# ATtiny841_StepperTesting.net
KiCad netlist of a schematic drawn in EAGLE
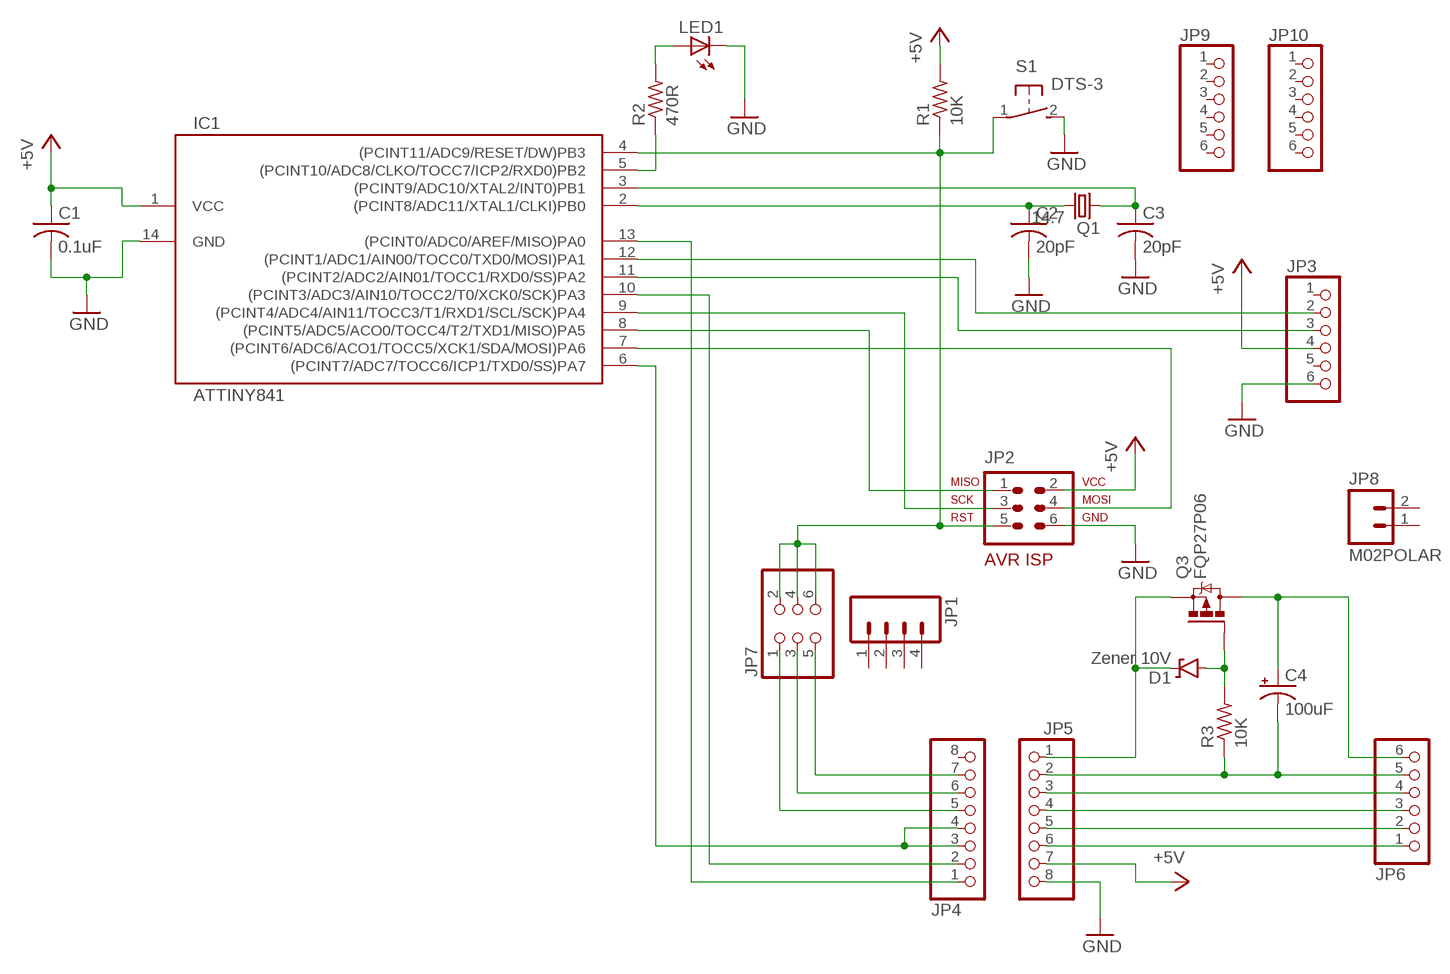
[diagram p0: schematic, sheet 1]

(export (version "E")
  (design (tool "Eeschema 10.0.6"))
  (components
    (comp (ref "C1")
      (value "0.1uF")
      (footprint "eagle-import:C025-024X044")
      (libsource (lib "eagle-import") (part "C025"))
    )
    (comp (ref "C2")
      (value "20pF")
      (footprint "eagle-import:C025-024X044")
      (libsource (lib "eagle-import") (part "C025"))
    )
    (comp (ref "C3")
      (value "20pF")
      (footprint "eagle-import:C025-024X044")
      (libsource (lib "eagle-import") (part "C025"))
    )
    (comp (ref "C4")
      (value "100uF")
      (footprint "eagle-import:E3,5-8")
      (libsource (lib "eagle-import") (part "CPOL-USE3.5-8"))
    )
    (comp (ref "D1")
      (value "Zener 10V")
      (footprint "eagle-import:DIODE-ZENER")
      (libsource (lib "eagle-import") (part "DIODE-ZENERPTH"))
    )
    (comp (ref "IC1")
      (value "ATTINY841")
      (footprint "eagle-import:SOIC14")
      (libsource (lib "eagle-import") (part "ATTINY441/841-SSU"))
    )
    (comp (ref "JP1")
      (value "M04POLAR")
      (footprint "eagle-import:MOLEX-1X4")
      (libsource (lib "eagle-import") (part "M04POLAR"))
    )
    (comp (ref "JP2")
      (value "AVR-ISP-6VERT")
      (footprint "eagle-import:AVR-ISP-6")
      (libsource (lib "eagle-import") (part "AVR-ISP-6VERT"))
    )
    (comp (ref "JP3")
      (value "PINHD-1X6CB")
      (footprint "eagle-import:1X06-CLEANBIG")
      (libsource (lib "eagle-import") (part "PINHD-1X6CB"))
    )
    (comp (ref "JP4")
      (value "PINHD-1X8CLEANBIG")
      (footprint "eagle-import:1X08-CLEANBIG")
      (libsource (lib "eagle-import") (part "PINHD-1X8CLEANBIG"))
    )
    (comp (ref "JP5")
      (value "PINHD-1X8CLEANBIG")
      (footprint "eagle-import:1X08-CLEANBIG")
      (libsource (lib "eagle-import") (part "PINHD-1X8CLEANBIG"))
    )
    (comp (ref "JP6")
      (value "PINHD-1X6CB")
      (footprint "eagle-import:1X06-CLEANBIG")
      (libsource (lib "eagle-import") (part "PINHD-1X6CB"))
    )
    (comp (ref "JP7")
      (value "PINHD-2X3")
      (footprint "eagle-import:2X03")
      (libsource (lib "eagle-import") (part "PINHD-2X3"))
    )
    (comp (ref "JP8")
      (value "M02POLAR")
      (footprint "eagle-import:MOLEX-1X2")
      (libsource (lib "eagle-import") (part "M02POLAR"))
    )
    (comp (ref "JP9")
      (value "PINHD-1X6CB")
      (footprint "eagle-import:1X06-CLEANBIG")
      (libsource (lib "eagle-import") (part "PINHD-1X6CB"))
    )
    (comp (ref "JP10")
      (value "PINHD-1X6CB")
      (footprint "eagle-import:1X06-CLEANBIG")
      (libsource (lib "eagle-import") (part "PINHD-1X6CB"))
    )
    (comp (ref "LED1")
      (value "LED5MM")
      (footprint "eagle-import:LED5MM")
      (libsource (lib "eagle-import") (part "LED5MM"))
    )
    (comp (ref "Q1")
      (value "14.7")
      (footprint "eagle-import:HC49_S")
      (libsource (lib "eagle-import") (part "CRYSTALHC49S"))
    )
    (comp (ref "Q3")
      (value "FQP27P06")
      (footprint "eagle-import:TO220BV")
      (libsource (lib "eagle-import") (part "IRF9530"))
    )
    (comp (ref "R1")
      (value "10K")
      (footprint "eagle-import:0207_7")
      (libsource (lib "eagle-import") (part "R-US_0207/7"))
    )
    (comp (ref "R2")
      (value "470R")
      (footprint "eagle-import:0207_7")
      (libsource (lib "eagle-import") (part "R-US_0207/7"))
    )
    (comp (ref "R3")
      (value "10K")
      (footprint "eagle-import:0207_7")
      (libsource (lib "eagle-import") (part "R-US_0207/7"))
    )
    (comp (ref "S1")
      (value "DTS-3")
      (footprint "eagle-import:DTS-3")
      (libsource (lib "eagle-import") (part "DTS-3"))
    )
  )
  (nets
    (net (code "1") (name "+5V") (class "Default")
      (node (ref "C1") (pin "1") (pinfunction "1_1") (pintype "passive"))
      (node (ref "IC1") (pin "1") (pinfunction "VCC_1") (pintype "bidirectional"))
      (node (ref "JP2") (pin "2") (pinfunction "2_2") (pintype "passive"))
      (node (ref "JP3") (pin "4") (pinfunction "4_4") (pintype "passive"))
      (node (ref "JP5") (pin "7") (pinfunction "7_7") (pintype "passive"))
      (node (ref "R1") (pin "2") (pinfunction "2_2") (pintype "passive"))
    )
    (net (code "2") (name "GND") (class "Default")
      (node (ref "C1") (pin "2") (pinfunction "2_2") (pintype "passive"))
      (node (ref "C2") (pin "2") (pinfunction "2_2") (pintype "passive"))
      (node (ref "C3") (pin "2") (pinfunction "2_2") (pintype "passive"))
      (node (ref "IC1") (pin "14") (pinfunction "GND_14") (pintype "bidirectional"))
      (node (ref "JP2") (pin "6") (pinfunction "6_6") (pintype "passive"))
      (node (ref "JP3") (pin "6") (pinfunction "6_6") (pintype "passive"))
      (node (ref "JP5") (pin "8") (pinfunction "8_8") (pintype "passive"))
      (node (ref "LED1") (pin "K") (pinfunction "C_K") (pintype "passive"))
      (node (ref "S1") (pin "2") (pinfunction "2_2") (pintype "passive"))
    )
    (net (code "3") (name "Net-(C4-Pad+)") (class "Default")
      (node (ref "C4") (pin "+") (pinfunction "+_+") (pintype "passive"))
      (node (ref "JP6") (pin "6") (pinfunction "6_6") (pintype "passive"))
      (node (ref "Q3") (pin "D") (pinfunction "D_D") (pintype "passive"))
    )
    (net (code "4") (name "Net-(C4-Pad-)") (class "Default")
      (node (ref "C4") (pin "-") (pinfunction "-_-") (pintype "passive"))
      (node (ref "JP5") (pin "2") (pinfunction "2_2") (pintype "passive"))
      (node (ref "JP6") (pin "5") (pinfunction "5_5") (pintype "passive"))
      (node (ref "R3") (pin "1") (pinfunction "1_1") (pintype "passive"))
    )
    (net (code "5") (name "Net-(D1-A)") (class "Default")
      (node (ref "D1") (pin "P$2") (pinfunction "A_P$2") (pintype "passive"))
      (node (ref "Q3") (pin "G") (pinfunction "G_G") (pintype "passive"))
      (node (ref "R3") (pin "2") (pinfunction "2_2") (pintype "passive"))
    )
    (net (code "6") (name "Net-(D1-C)") (class "Default")
      (node (ref "D1") (pin "P$1") (pinfunction "C_P$1") (pintype "passive"))
      (node (ref "JP5") (pin "1") (pinfunction "1_1") (pintype "passive"))
      (node (ref "Q3") (pin "S") (pinfunction "S_S") (pintype "passive"))
    )
    (net (code "7") (name "Net-(IC1-(PCINT0{slash}ADC0{slash}AREF{slash}MISO)PA0)") (class "Default")
      (node (ref "IC1") (pin "13") (pinfunction "(PCINT0/ADC0/AREF/MISO)PA0_13") (pintype "bidirectional"))
      (node (ref "JP4") (pin "1") (pinfunction "1_1") (pintype "passive"))
    )
    (net (code "8") (name "Net-(IC1-(PCINT1{slash}ADC1{slash}AIN00{slash}TOCC0{slash}TXD0{slash}MOSI)PA1)") (class "Default")
      (node (ref "IC1") (pin "12") (pinfunction "(PCINT1/ADC1/AIN00/TOCC0/TXD0/MOSI)PA1_12") (pintype "bidirectional"))
      (node (ref "JP3") (pin "2") (pinfunction "2_2") (pintype "passive"))
    )
    (net (code "9") (name "Net-(IC1-(PCINT2{slash}ADC2{slash}AIN01{slash}TOCC1{slash}RXD0{slash}SS)PA2)") (class "Default")
      (node (ref "IC1") (pin "11") (pinfunction "(PCINT2/ADC2/AIN01/TOCC1/RXD0/SS)PA2_11") (pintype "bidirectional"))
      (node (ref "JP3") (pin "3") (pinfunction "3_3") (pintype "passive"))
    )
    (net (code "10") (name "Net-(IC1-(PCINT3{slash}ADC3{slash}AIN10{slash}TOCC2{slash}T0{slash}XCK0{slash}SCK)PA3)") (class "Default")
      (node (ref "IC1") (pin "10") (pinfunction "(PCINT3/ADC3/AIN10/TOCC2/T0/XCK0/SCK)PA3_10") (pintype "bidirectional"))
      (node (ref "JP4") (pin "2") (pinfunction "2_2") (pintype "passive"))
    )
    (net (code "11") (name "Net-(IC1-(PCINT4{slash}ADC4{slash}AIN11{slash}TOCC3{slash}T1{slash}RXD1{slash}SCL{slash}SCK)PA4)") (class "Default")
      (node (ref "IC1") (pin "9") (pinfunction "(PCINT4/ADC4/AIN11/TOCC3/T1/RXD1/SCL/SCK)PA4_9") (pintype "bidirectional"))
      (node (ref "JP2") (pin "3") (pinfunction "3_3") (pintype "passive"))
    )
    (net (code "12") (name "Net-(IC1-(PCINT5{slash}ADC5{slash}ACO0{slash}TOCC4{slash}T2{slash}TXD1{slash}MISO)PA5)") (class "Default")
      (node (ref "IC1") (pin "8") (pinfunction "(PCINT5/ADC5/ACO0/TOCC4/T2/TXD1/MISO)PA5_8") (pintype "bidirectional"))
      (node (ref "JP2") (pin "1") (pinfunction "1_1") (pintype "passive"))
    )
    (net (code "13") (name "Net-(IC1-(PCINT6{slash}ADC6{slash}ACO1{slash}TOCC5{slash}XCK1{slash}SDA{slash}MOSI)PA6)") (class "Default")
      (node (ref "IC1") (pin "7") (pinfunction "(PCINT6/ADC6/ACO1/TOCC5/XCK1/SDA/MOSI)PA6_7") (pintype "bidirectional"))
      (node (ref "JP2") (pin "4") (pinfunction "4_4") (pintype "passive"))
    )
    (net (code "14") (name "Net-(IC1-(PCINT7{slash}ADC7{slash}TOCC6{slash}ICP1{slash}TXD0{slash}SS)PA7)") (class "Default")
      (node (ref "IC1") (pin "6") (pinfunction "(PCINT7/ADC7/TOCC6/ICP1/TXD0/SS)PA7_6") (pintype "bidirectional"))
      (node (ref "JP4") (pin "3") (pinfunction "3_3") (pintype "passive"))
      (node (ref "JP4") (pin "4") (pinfunction "4_4") (pintype "passive"))
    )
    (net (code "15") (name "Net-(IC1-(PCINT8{slash}ADC11{slash}XTAL1{slash}CLKI)PB0)") (class "Default")
      (node (ref "C2") (pin "1") (pinfunction "1_1") (pintype "passive"))
      (node (ref "IC1") (pin "2") (pinfunction "(PCINT8/ADC11/XTAL1/CLKI)PB0_2") (pintype "bidirectional"))
      (node (ref "Q1") (pin "2") (pinfunction "2_2") (pintype "passive"))
    )
    (net (code "16") (name "Net-(IC1-(PCINT9{slash}ADC10{slash}XTAL2{slash}INT0)PB1)") (class "Default")
      (node (ref "C3") (pin "1") (pinfunction "1_1") (pintype "passive"))
      (node (ref "IC1") (pin "3") (pinfunction "(PCINT9/ADC10/XTAL2/INT0)PB1_3") (pintype "bidirectional"))
      (node (ref "Q1") (pin "1") (pinfunction "1_1") (pintype "passive"))
    )
    (net (code "17") (name "Net-(IC1-(PCINT10{slash}ADC8{slash}CLKO{slash}TOCC7{slash}ICP2{slash}RXD0)PB2)") (class "Default")
      (node (ref "IC1") (pin "5") (pinfunction "(PCINT10/ADC8/CLKO/TOCC7/ICP2/RXD0)PB2_5") (pintype "bidirectional"))
      (node (ref "R2") (pin "1") (pinfunction "1_1") (pintype "passive"))
    )
    (net (code "18") (name "Net-(IC1-(PCINT11{slash}ADC9{slash}RESET{slash}DW)PB3)") (class "Default")
      (node (ref "IC1") (pin "4") (pinfunction "(PCINT11/ADC9/RESET/DW)PB3_4") (pintype "bidirectional"))
      (node (ref "JP2") (pin "5") (pinfunction "5_5") (pintype "passive"))
      (node (ref "JP7") (pin "2") (pinfunction "2_2") (pintype "passive"))
      (node (ref "JP7") (pin "4") (pinfunction "4_4") (pintype "passive"))
      (node (ref "JP7") (pin "6") (pinfunction "6_6") (pintype "passive"))
      (node (ref "R1") (pin "1") (pinfunction "1_1") (pintype "passive"))
      (node (ref "S1") (pin "1") (pinfunction "1_1") (pintype "passive"))
    )
    (net (code "19") (name "Net-(JP4-Pad5)") (class "Default")
      (node (ref "JP4") (pin "5") (pinfunction "5_5") (pintype "passive"))
      (node (ref "JP7") (pin "1") (pinfunction "1_1") (pintype "passive"))
    )
    (net (code "20") (name "Net-(JP4-Pad6)") (class "Default")
      (node (ref "JP4") (pin "6") (pinfunction "6_6") (pintype "passive"))
      (node (ref "JP7") (pin "3") (pinfunction "3_3") (pintype "passive"))
    )
    (net (code "21") (name "Net-(JP4-Pad7)") (class "Default")
      (node (ref "JP4") (pin "7") (pinfunction "7_7") (pintype "passive"))
      (node (ref "JP7") (pin "5") (pinfunction "5_5") (pintype "passive"))
    )
    (net (code "22") (name "Net-(JP5-Pad3)") (class "Default")
      (node (ref "JP5") (pin "3") (pinfunction "3_3") (pintype "passive"))
      (node (ref "JP6") (pin "4") (pinfunction "4_4") (pintype "passive"))
    )
    (net (code "23") (name "Net-(JP5-Pad4)") (class "Default")
      (node (ref "JP5") (pin "4") (pinfunction "4_4") (pintype "passive"))
      (node (ref "JP6") (pin "3") (pinfunction "3_3") (pintype "passive"))
    )
    (net (code "24") (name "Net-(JP5-Pad5)") (class "Default")
      (node (ref "JP5") (pin "5") (pinfunction "5_5") (pintype "passive"))
      (node (ref "JP6") (pin "2") (pinfunction "2_2") (pintype "passive"))
    )
    (net (code "25") (name "Net-(JP5-Pad6)") (class "Default")
      (node (ref "JP5") (pin "6") (pinfunction "6_6") (pintype "passive"))
      (node (ref "JP6") (pin "1") (pinfunction "1_1") (pintype "passive"))
    )
    (net (code "26") (name "Net-(LED1-PadA)") (class "Default")
      (node (ref "LED1") (pin "A") (pinfunction "A_A") (pintype "passive"))
      (node (ref "R2") (pin "2") (pinfunction "2_2") (pintype "passive"))
    )
    (net (code "27") (name "unconnected-(JP1-Pad1)") (class "Default")
      (node (ref "JP1") (pin "1") (pinfunction "1_1") (pintype "passive"))
    )
    (net (code "28") (name "unconnected-(JP1-Pad2)") (class "Default")
      (node (ref "JP1") (pin "2") (pinfunction "2_2") (pintype "passive"))
    )
    (net (code "29") (name "unconnected-(JP1-Pad3)") (class "Default")
      (node (ref "JP1") (pin "3") (pinfunction "3_3") (pintype "passive"))
    )
    (net (code "30") (name "unconnected-(JP1-Pad4)") (class "Default")
      (node (ref "JP1") (pin "4") (pinfunction "4_4") (pintype "passive"))
    )
    (net (code "31") (name "unconnected-(JP3-Pad1)") (class "Default")
      (node (ref "JP3") (pin "1") (pinfunction "1_1") (pintype "passive"))
    )
    (net (code "32") (name "unconnected-(JP3-Pad5)") (class "Default")
      (node (ref "JP3") (pin "5") (pinfunction "5_5") (pintype "passive"))
    )
    (net (code "33") (name "unconnected-(JP4-Pad8)") (class "Default")
      (node (ref "JP4") (pin "8") (pinfunction "8_8") (pintype "passive"))
    )
    (net (code "34") (name "unconnected-(JP8-Pad1)") (class "Default")
      (node (ref "JP8") (pin "1") (pinfunction "1_1") (pintype "passive"))
    )
    (net (code "35") (name "unconnected-(JP8-Pad2)") (class "Default")
      (node (ref "JP8") (pin "2") (pinfunction "2_2") (pintype "passive"))
    )
    (net (code "36") (name "unconnected-(JP9-Pad1)") (class "Default")
      (node (ref "JP9") (pin "1") (pinfunction "1_1") (pintype "passive"))
    )
    (net (code "37") (name "unconnected-(JP9-Pad2)") (class "Default")
      (node (ref "JP9") (pin "2") (pinfunction "2_2") (pintype "passive"))
    )
    (net (code "38") (name "unconnected-(JP9-Pad3)") (class "Default")
      (node (ref "JP9") (pin "3") (pinfunction "3_3") (pintype "passive"))
    )
    (net (code "39") (name "unconnected-(JP9-Pad4)") (class "Default")
      (node (ref "JP9") (pin "4") (pinfunction "4_4") (pintype "passive"))
    )
    (net (code "40") (name "unconnected-(JP9-Pad5)") (class "Default")
      (node (ref "JP9") (pin "5") (pinfunction "5_5") (pintype "passive"))
    )
    (net (code "41") (name "unconnected-(JP9-Pad6)") (class "Default")
      (node (ref "JP9") (pin "6") (pinfunction "6_6") (pintype "passive"))
    )
    (net (code "42") (name "unconnected-(JP10-Pad1)") (class "Default")
      (node (ref "JP10") (pin "1") (pinfunction "1_1") (pintype "passive"))
    )
    (net (code "43") (name "unconnected-(JP10-Pad2)") (class "Default")
      (node (ref "JP10") (pin "2") (pinfunction "2_2") (pintype "passive"))
    )
    (net (code "44") (name "unconnected-(JP10-Pad3)") (class "Default")
      (node (ref "JP10") (pin "3") (pinfunction "3_3") (pintype "passive"))
    )
    (net (code "45") (name "unconnected-(JP10-Pad4)") (class "Default")
      (node (ref "JP10") (pin "4") (pinfunction "4_4") (pintype "passive"))
    )
    (net (code "46") (name "unconnected-(JP10-Pad5)") (class "Default")
      (node (ref "JP10") (pin "5") (pinfunction "5_5") (pintype "passive"))
    )
    (net (code "47") (name "unconnected-(JP10-Pad6)") (class "Default")
      (node (ref "JP10") (pin "6") (pinfunction "6_6") (pintype "passive"))
    )
  )
)
